# KA2_4.net
KiCad netlist of a schematic drawn in Altium Designer
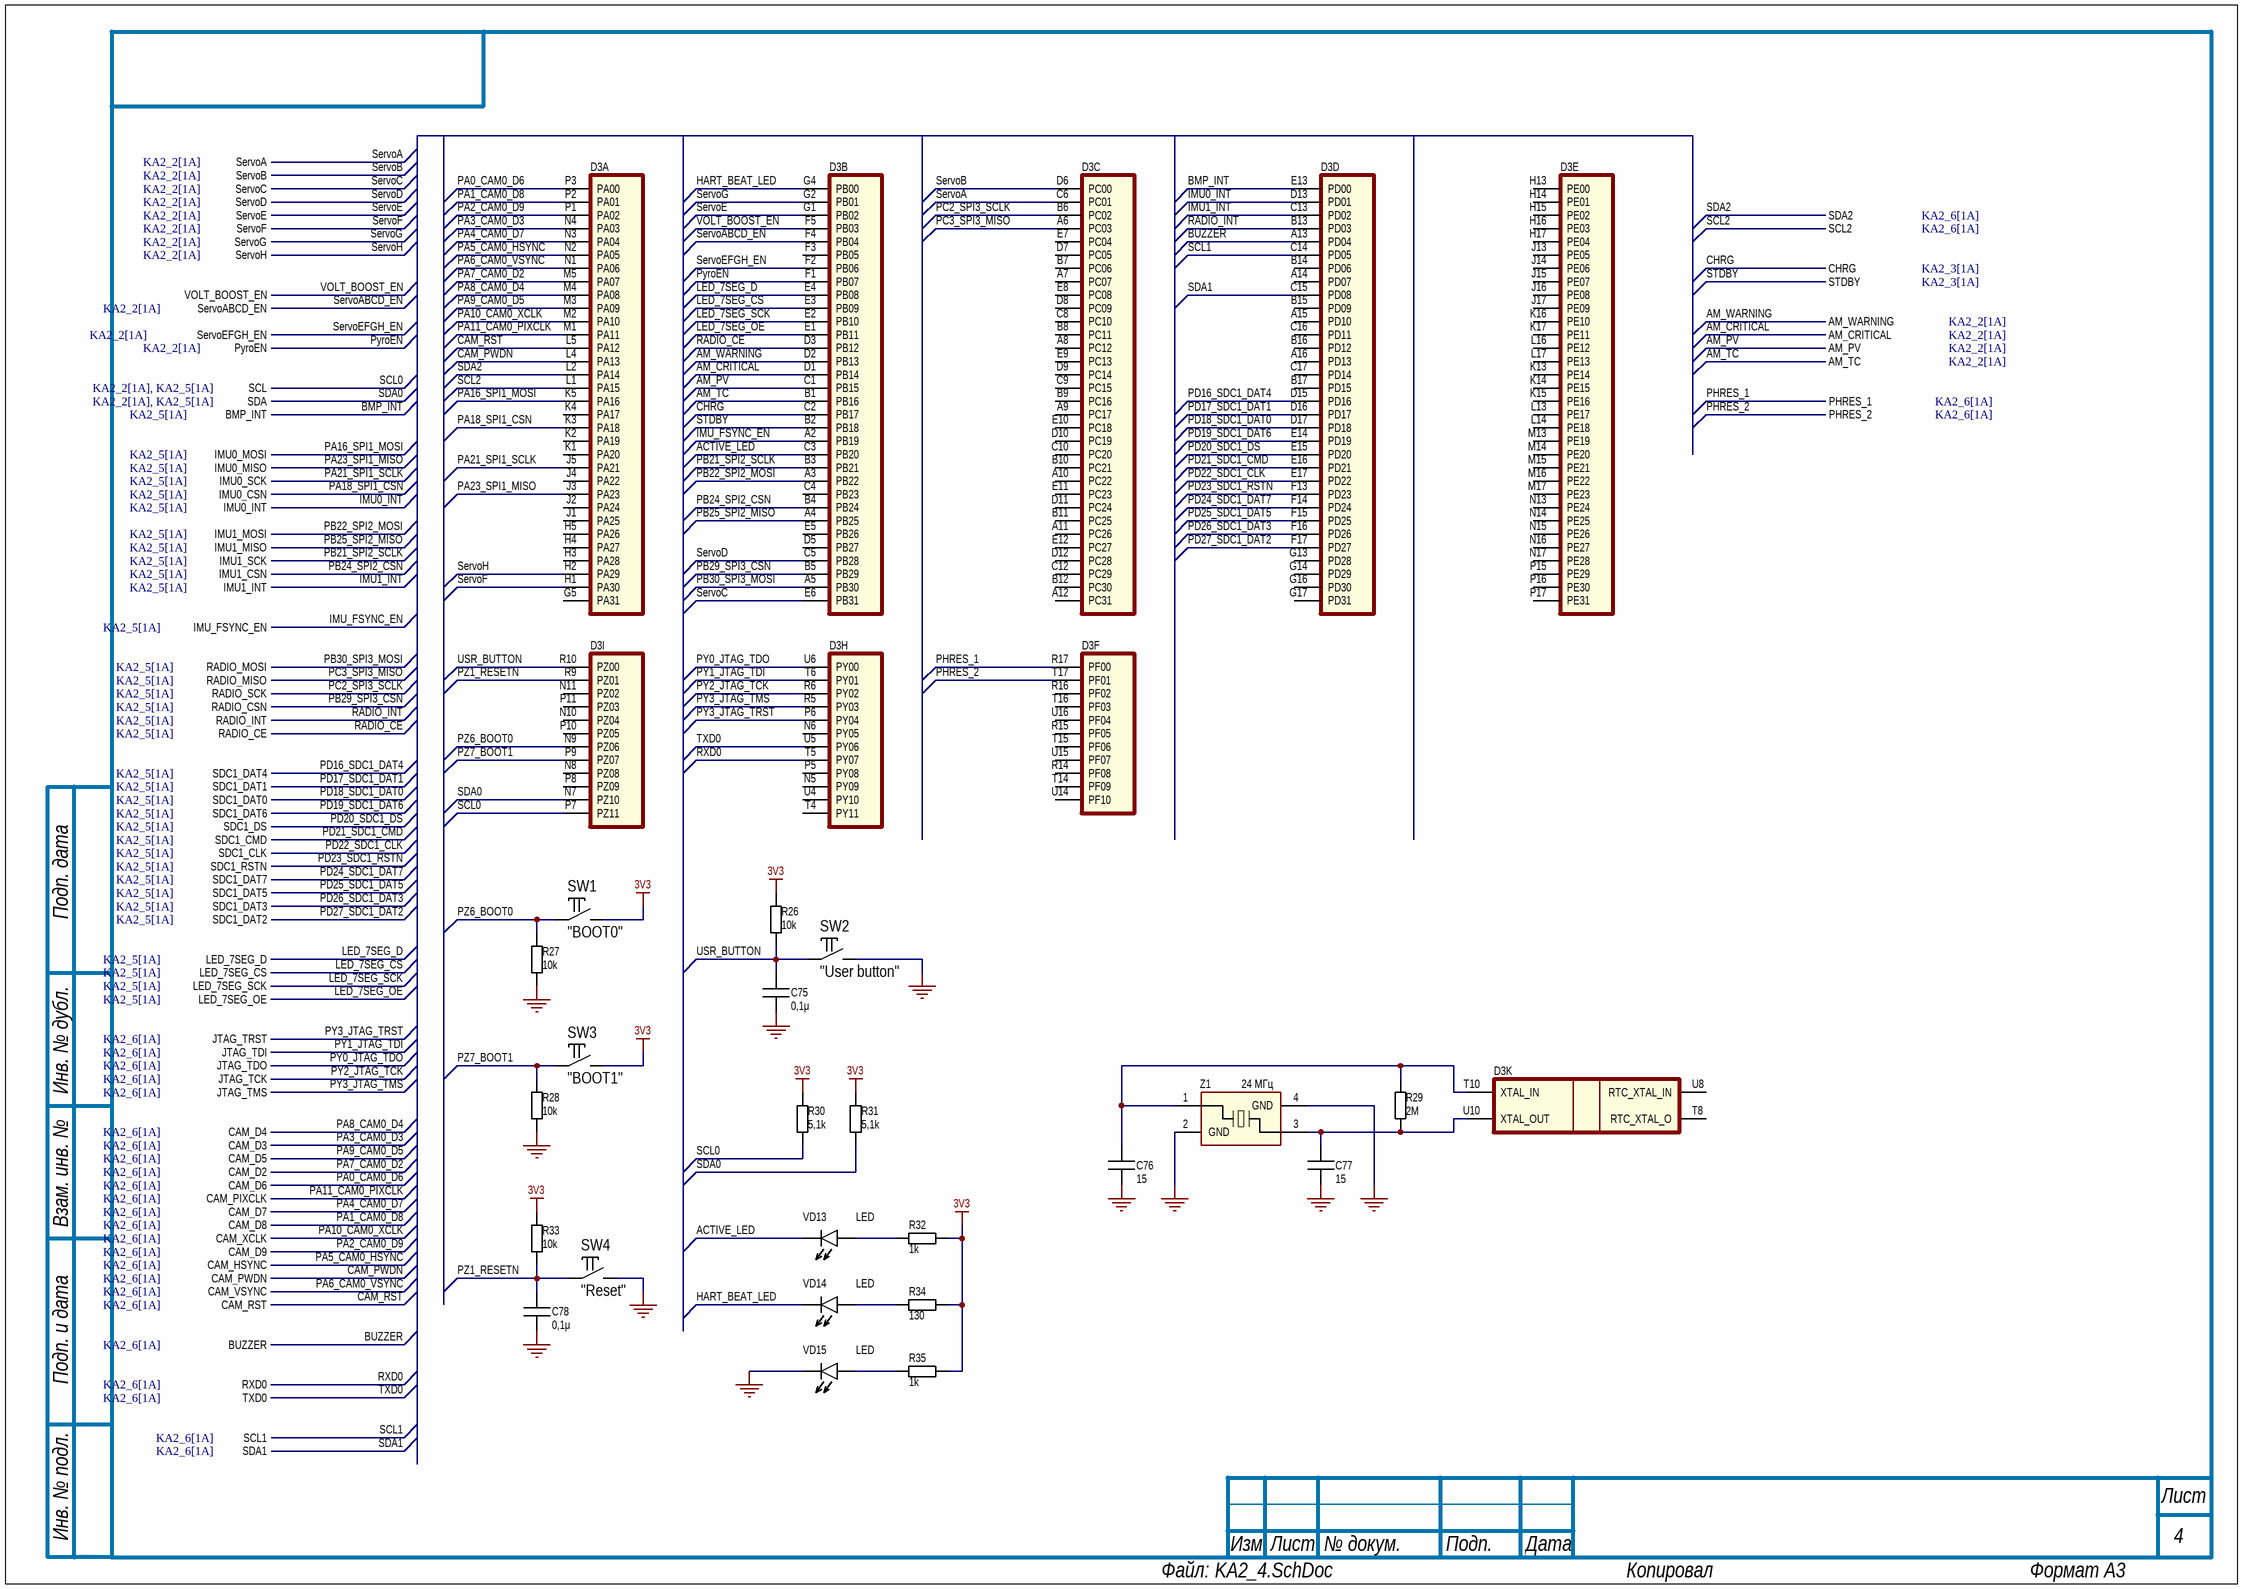
[diagram p0: KA2_4.SchDoc]

(export (version "E")
  (design (tool "Eeschema 10.0.6"))
  (components
    (comp (ref "C75")
      (value "0,1μ")
      (footprint "Capacitor_0402")
      (fields
        (field (name "VALUEMANUFACTURERPARTNUMBER") "Ceramic capacitor, 0,1μ, X7R, ±10%, 16V, 0402")
        (field (name "TOLERANCE") "±10%")
        (field (name "VOLTAGE") "16V")
      )
      (libsource (lib "Barsotion") (part "Ceramic_0402"))
    )
    (comp (ref "C76")
      (value "15")
      (footprint "Capacitor_0402")
      (fields
        (field (name "VALUEMANUFACTURERPARTNUMBER") "Ceramic capacitor, 15, X7R, ±10%, 16V, 0402")
        (field (name "TOLERANCE") "±10%")
        (field (name "VOLTAGE") "16V")
      )
      (libsource (lib "Barsotion") (part "Ceramic_0402"))
    )
    (comp (ref "C77")
      (value "15")
      (footprint "Capacitor_0402")
      (fields
        (field (name "VALUEMANUFACTURERPARTNUMBER") "Ceramic capacitor, 15, X7R, ±10%, 16V, 0402")
        (field (name "TOLERANCE") "±10%")
        (field (name "VOLTAGE") "16V")
      )
      (libsource (lib "Barsotion") (part "Ceramic_0402"))
    )
    (comp (ref "C78")
      (value "0,1μ")
      (footprint "Capacitor_0402")
      (fields
        (field (name "VALUEMANUFACTURERPARTNUMBER") "Ceramic capacitor, 0,1μ, X7R, ±10%, 16V, 0402")
        (field (name "TOLERANCE") "±10%")
        (field (name "VOLTAGE") "16V")
      )
      (libsource (lib "Barsotion") (part "Ceramic_0402"))
    )
    (comp (ref "D3")
      (value "HPM6754IVM2")
      (footprint "HPM6754IVM2_BGA-289_14x14mm")
      (description "Микроконтроллер RISC-V, 2xRV32GCBP@816МГц, 2МБ ОЗУ, BGA-289 14x14mm")
      (fields (field (name "MANUFACTURER") "HPMICRO"))
      (libsource (lib "Barsotion") (part "HPM6754IVM2"))
    )
    (comp (ref "R26")
      (value "10k")
      (footprint "RES: 0402")
      (fields
        (field (name "VALUEMANUFACTURERPARTNUMBER") "Resistor, 10k, ±1%, 0402")
        (field (name "TOLERANCE") "±1%")
      )
      (libsource (lib "Barsotion") (part "Resistor_0402"))
    )
    (comp (ref "R27")
      (value "10k")
      (footprint "RES: 0402")
      (fields
        (field (name "VALUEMANUFACTURERPARTNUMBER") "Resistor, 10k, ±1%, 0402")
        (field (name "TOLERANCE") "±1%")
      )
      (libsource (lib "Barsotion") (part "Resistor_0402"))
    )
    (comp (ref "R28")
      (value "10k")
      (footprint "RES: 0402")
      (fields
        (field (name "VALUEMANUFACTURERPARTNUMBER") "Resistor, 10k, ±1%, 0402")
        (field (name "TOLERANCE") "±1%")
      )
      (libsource (lib "Barsotion") (part "Resistor_0402"))
    )
    (comp (ref "R29")
      (value "2M")
      (footprint "RES: 0402")
      (fields
        (field (name "VALUEMANUFACTURERPARTNUMBER") "Resistor, 2M, ±1%, 0402")
        (field (name "TOLERANCE") "±1%")
      )
      (libsource (lib "Barsotion") (part "Resistor_0402"))
    )
    (comp (ref "R30")
      (value "5,1k")
      (footprint "RES: 0402")
      (fields
        (field (name "VALUEMANUFACTURERPARTNUMBER") "Resistor, 5,1k, ±1%, 0402")
        (field (name "TOLERANCE") "±1%")
      )
      (libsource (lib "Barsotion") (part "Resistor_0402"))
    )
    (comp (ref "R31")
      (value "5,1k")
      (footprint "RES: 0402")
      (fields
        (field (name "VALUEMANUFACTURERPARTNUMBER") "Resistor, 5,1k, ±1%, 0402")
        (field (name "TOLERANCE") "±1%")
      )
      (libsource (lib "Barsotion") (part "Resistor_0402"))
    )
    (comp (ref "R32")
      (value "1k")
      (footprint "RES: 0402")
      (fields
        (field (name "VALUEMANUFACTURERPARTNUMBER") "Resistor, 1k, ±1%, 0402")
        (field (name "TOLERANCE") "±1%")
      )
      (libsource (lib "") (part "Resistor_0402_1"))
    )
    (comp (ref "R33")
      (value "10k")
      (footprint "RES: 0402")
      (fields
        (field (name "VALUEMANUFACTURERPARTNUMBER") "Resistor, 10k, ±1%, 0402")
        (field (name "TOLERANCE") "±1%")
      )
      (libsource (lib "Barsotion") (part "Resistor_0402"))
    )
    (comp (ref "R34")
      (value "130")
      (footprint "RES: 0402")
      (fields
        (field (name "VALUEMANUFACTURERPARTNUMBER") "Resistor, 130, ±1%, 0402")
        (field (name "TOLERANCE") "±1%")
      )
      (libsource (lib "") (part "Resistor_0402_1"))
    )
    (comp (ref "R35")
      (value "1k")
      (footprint "RES: 0402")
      (fields
        (field (name "VALUEMANUFACTURERPARTNUMBER") "Resistor, 1k, ±1%, 0402")
        (field (name "TOLERANCE") "±1%")
      )
      (libsource (lib "") (part "Resistor_0402_1"))
    )
    (comp (ref "SW1")
      (value "Tactile Switch SPST 400gf 2.5mm 4.2mm x 3.2mm Surface Mount")
      (footprint "Button_4.2x2.3mm")
      (description "Микропереключатель SMD, SMD-4P,4.2x3.2mm")
      (fields
        (field (name "MANUFACTURER") "G-Switch")
        (field (name "COMMENTTEXT") "\"BOOT0\"")
        (field (name "MFR.PART") "GT-TC048D-H025-L1")
      )
      (libsource (lib "Barsotion") (part "Switch_GT-TC048D-H025-L1"))
    )
    (comp (ref "SW2")
      (value "Tactile Switch SPST 400gf 2.5mm 4.2mm x 3.2mm Surface Mount")
      (footprint "Button_4.2x2.3mm")
      (description "Микропереключатель SMD, SMD-4P,4.2x3.2mm")
      (fields
        (field (name "MANUFACTURER") "G-Switch")
        (field (name "COMMENTTEXT") "\"User button\"")
        (field (name "MFR.PART") "GT-TC048D-H025-L1")
      )
      (libsource (lib "Barsotion") (part "Switch_GT-TC048D-H025-L1"))
    )
    (comp (ref "SW3")
      (value "Tactile Switch SPST 400gf 2.5mm 4.2mm x 3.2mm Surface Mount")
      (footprint "Button_4.2x2.3mm")
      (description "Микропереключатель SMD, SMD-4P,4.2x3.2mm")
      (fields
        (field (name "MANUFACTURER") "G-Switch")
        (field (name "COMMENTTEXT") "\"BOOT1\"")
        (field (name "MFR.PART") "GT-TC048D-H025-L1")
      )
      (libsource (lib "Barsotion") (part "Switch_GT-TC048D-H025-L1"))
    )
    (comp (ref "SW4")
      (value "Tactile Switch SPST 400gf 2.5mm 4.2mm x 3.2mm Surface Mount")
      (footprint "Button_4.2x2.3mm")
      (description "Микропереключатель SMD, SMD-4P,4.2x3.2mm")
      (fields
        (field (name "MANUFACTURER") "G-Switch")
        (field (name "COMMENTTEXT") "\"Reset\"")
        (field (name "MFR.PART") "GT-TC048D-H025-L1")
      )
      (libsource (lib "Barsotion") (part "Switch_GT-TC048D-H025-L1"))
    )
    (comp (ref "VD13")
      (value "LED")
      (footprint "LED: 0603Y")
      (description "Светодиод желтый, 0603")
      (fields (field (name "MFR.PART") "TJ-S1608CY6T5ALC9Y-A5") (field (name "MANUFACTURER") "TOGIALED"))
      (libsource (lib "Barsotion") (part "LED_0603_Y"))
    )
    (comp (ref "VD14")
      (value "LED")
      (footprint "LED: 0603Y")
      (description "Светодиод белый, 0603")
      (fields (field (name "MFR.PART") "TZ0603W3G-001/2#") (field (name "MANUFACTURER") "TUOZHAN"))
      (libsource (lib "Barsotion") (part "LED_0603_W"))
    )
    (comp (ref "VD15")
      (value "LED")
      (footprint "LED: 0603Y")
      (description "Светодиод желтый, 0603")
      (fields (field (name "MFR.PART") "TJ-S1608CY6T5ALC9Y-A5") (field (name "MANUFACTURER") "TOGIALED"))
      (libsource (lib "Barsotion") (part "LED_0603_Y"))
    )
    (comp (ref "Z1")
      (value "24 МГц")
      (footprint "OSC: 2016")
      (description "Кварцевый резонатор 24 МГц 2016")
      (fields
        (field (name "MFR.PART") "XL7EL89CKI-111YLC-24M")
        (field (name "MANUFACTURER") "YXC Crystal Oscillators")
      )
      (libsource (lib "Barsotion") (part "Crystal_XL7EL89CKI-111YLC-24M"))
    )
  )
  (nets
    (net (code "1") (name "/ACTIVE_LED") (class "Default")
      (node (ref "D3") (pin "C3") (pinfunction "PB20_C3") (pintype "passive"))
      (node (ref "VD13") (pin "K") (pinfunction "Kathode_K") (pintype "passive"))
    )
    (net (code "2") (name "/AM_CRITICAL") (class "Default")
      (node (ref "D3") (pin "D1") (pinfunction "PB14_D1") (pintype "passive"))
    )
    (net (code "3") (name "/AM_PV") (class "Default")
      (node (ref "D3") (pin "C1") (pinfunction "PB15_C1") (pintype "passive"))
    )
    (net (code "4") (name "/AM_TC") (class "Default")
      (node (ref "D3") (pin "B1") (pinfunction "PB16_B1") (pintype "passive"))
    )
    (net (code "5") (name "/AM_WARNING") (class "Default")
      (node (ref "D3") (pin "D2") (pinfunction "PB13_D2") (pintype "passive"))
    )
    (net (code "6") (name "/BMP_INT") (class "Default")
      (node (ref "D3") (pin "E13") (pinfunction "PD00_E13") (pintype "passive"))
    )
    (net (code "7") (name "/BUZZER") (class "Default")
      (node (ref "D3") (pin "A13") (pinfunction "PD04_A13") (pintype "passive"))
    )
    (net (code "8") (name "/CAM_PWDN") (class "Default")
      (node (ref "D3") (pin "L4") (pinfunction "PA13_L4") (pintype "passive"))
    )
    (net (code "9") (name "/CAM_RST") (class "Default")
      (node (ref "D3") (pin "L5") (pinfunction "PA12_L5") (pintype "passive"))
    )
    (net (code "10") (name "/CHRG") (class "Default")
      (node (ref "D3") (pin "C2") (pinfunction "PB17_C2") (pintype "passive"))
    )
    (net (code "11") (name "/HART_BEAT_LED") (class "Default")
      (node (ref "D3") (pin "G4") (pinfunction "PB00_G4") (pintype "passive"))
      (node (ref "VD14") (pin "K") (pinfunction "Kathode_K") (pintype "passive"))
    )
    (net (code "12") (name "/IMU0_INT") (class "Default")
      (node (ref "D3") (pin "D13") (pinfunction "PD01_D13") (pintype "passive"))
    )
    (net (code "13") (name "/IMU1_INT") (class "Default")
      (node (ref "D3") (pin "C13") (pinfunction "PD02_C13") (pintype "passive"))
    )
    (net (code "14") (name "/IMU_FSYNC_EN") (class "Default")
      (node (ref "D3") (pin "A2") (pinfunction "PB19_A2") (pintype "passive"))
    )
    (net (code "15") (name "/LED_7SEG_CS") (class "Default")
      (node (ref "D3") (pin "E3") (pinfunction "PB09_E3") (pintype "passive"))
    )
    (net (code "16") (name "/LED_7SEG_D") (class "Default")
      (node (ref "D3") (pin "E4") (pinfunction "PB08_E4") (pintype "passive"))
    )
    (net (code "17") (name "/LED_7SEG_OE") (class "Default")
      (node (ref "D3") (pin "E1") (pinfunction "PB11_E1") (pintype "passive"))
    )
    (net (code "18") (name "/LED_7SEG_SCK") (class "Default")
      (node (ref "D3") (pin "E2") (pinfunction "PB10_E2") (pintype "passive"))
    )
    (net (code "19") (name "/PA0_CAM0_D6") (class "Default")
      (node (ref "D3") (pin "P3") (pinfunction "PA00_P3") (pintype "passive"))
    )
    (net (code "20") (name "/PA1_CAM0_D8") (class "Default")
      (node (ref "D3") (pin "P2") (pinfunction "PA01_P2") (pintype "passive"))
    )
    (net (code "21") (name "/PA2_CAM0_D9") (class "Default")
      (node (ref "D3") (pin "P1") (pinfunction "PA02_P1") (pintype "passive"))
    )
    (net (code "22") (name "/PA3_CAM0_D3") (class "Default")
      (node (ref "D3") (pin "N4") (pinfunction "PA03_N4") (pintype "passive"))
    )
    (net (code "23") (name "/PA4_CAM0_D7") (class "Default")
      (node (ref "D3") (pin "N3") (pinfunction "PA04_N3") (pintype "passive"))
    )
    (net (code "24") (name "/PA5_CAM0_HSYNC") (class "Default")
      (node (ref "D3") (pin "N2") (pinfunction "PA05_N2") (pintype "passive"))
    )
    (net (code "25") (name "/PA6_CAM0_VSYNC") (class "Default")
      (node (ref "D3") (pin "N1") (pinfunction "PA06_N1") (pintype "passive"))
    )
    (net (code "26") (name "/PA7_CAM0_D2") (class "Default")
      (node (ref "D3") (pin "M5") (pinfunction "PA07_M5") (pintype "passive"))
    )
    (net (code "27") (name "/PA8_CAM0_D4") (class "Default")
      (node (ref "D3") (pin "M4") (pinfunction "PA08_M4") (pintype "passive"))
    )
    (net (code "28") (name "/PA9_CAM0_D5") (class "Default")
      (node (ref "D3") (pin "M3") (pinfunction "PA09_M3") (pintype "passive"))
    )
    (net (code "29") (name "/PA10_CAM0_XCLK") (class "Default")
      (node (ref "D3") (pin "M2") (pinfunction "PA10_M2") (pintype "passive"))
    )
    (net (code "30") (name "/PA11_CAM0_PIXCLK") (class "Default")
      (node (ref "D3") (pin "M1") (pinfunction "PA11_M1") (pintype "passive"))
    )
    (net (code "31") (name "/PA16_SPI1_MOSI") (class "Default")
      (node (ref "D3") (pin "K5") (pinfunction "PA16_K5") (pintype "passive"))
    )
    (net (code "32") (name "/PA18_SPI1_CSN") (class "Default")
      (node (ref "D3") (pin "K3") (pinfunction "PA18_K3") (pintype "passive"))
    )
    (net (code "33") (name "/PA21_SPI1_SCLK") (class "Default")
      (node (ref "D3") (pin "J5") (pinfunction "PA21_J5") (pintype "passive"))
    )
    (net (code "34") (name "/PA23_SPI1_MISO") (class "Default")
      (node (ref "D3") (pin "J3") (pinfunction "PA23_J3") (pintype "passive"))
    )
    (net (code "35") (name "/PB21_SPI2_SCLK") (class "Default")
      (node (ref "D3") (pin "B3") (pinfunction "PB21_B3") (pintype "passive"))
    )
    (net (code "36") (name "/PB22_SPI2_MOSI") (class "Default")
      (node (ref "D3") (pin "A3") (pinfunction "PB22_A3") (pintype "passive"))
    )
    (net (code "37") (name "/PB24_SPI2_CSN") (class "Default")
      (node (ref "D3") (pin "B4") (pinfunction "PB24_B4") (pintype "passive"))
    )
    (net (code "38") (name "/PB25_SPI2_MISO") (class "Default")
      (node (ref "D3") (pin "A4") (pinfunction "PB25_A4") (pintype "passive"))
    )
    (net (code "39") (name "/PB29_SPI3_CSN") (class "Default")
      (node (ref "D3") (pin "B5") (pinfunction "PB29_B5") (pintype "passive"))
    )
    (net (code "40") (name "/PB30_SPI3_MOSI") (class "Default")
      (node (ref "D3") (pin "A5") (pinfunction "PB30_A5") (pintype "passive"))
    )
    (net (code "41") (name "/PC2_SPI3_SCLK") (class "Default")
      (node (ref "D3") (pin "B6") (pinfunction "PC02_B6") (pintype "passive"))
    )
    (net (code "42") (name "/PC3_SPI3_MISO") (class "Default")
      (node (ref "D3") (pin "A6") (pinfunction "PC03_A6") (pintype "passive"))
    )
    (net (code "43") (name "/PD16_SDC1_DAT4") (class "Default")
      (node (ref "D3") (pin "D15") (pinfunction "PD16_D15") (pintype "passive"))
    )
    (net (code "44") (name "/PD17_SDC1_DAT1") (class "Default")
      (node (ref "D3") (pin "D16") (pinfunction "PD17_D16") (pintype "passive"))
    )
    (net (code "45") (name "/PD18_SDC1_DAT0") (class "Default")
      (node (ref "D3") (pin "D17") (pinfunction "PD18_D17") (pintype "passive"))
    )
    (net (code "46") (name "/PD19_SDC1_DAT6") (class "Default")
      (node (ref "D3") (pin "E14") (pinfunction "PD19_E14") (pintype "passive"))
    )
    (net (code "47") (name "/PD20_SDC1_DS") (class "Default")
      (node (ref "D3") (pin "E15") (pinfunction "PD20_E15") (pintype "passive"))
    )
    (net (code "48") (name "/PD21_SDC1_CMD") (class "Default")
      (node (ref "D3") (pin "E16") (pinfunction "PD21_E16") (pintype "passive"))
    )
    (net (code "49") (name "/PD22_SDC1_CLK") (class "Default")
      (node (ref "D3") (pin "E17") (pinfunction "PD22_E17") (pintype "passive"))
    )
    (net (code "50") (name "/PD23_SDC1_RSTN") (class "Default")
      (node (ref "D3") (pin "F13") (pinfunction "PD23_F13") (pintype "passive"))
    )
    (net (code "51") (name "/PD24_SDC1_DAT7") (class "Default")
      (node (ref "D3") (pin "F14") (pinfunction "PD24_F14") (pintype "passive"))
    )
    (net (code "52") (name "/PD25_SDC1_DAT5") (class "Default")
      (node (ref "D3") (pin "F15") (pinfunction "PD25_F15") (pintype "passive"))
    )
    (net (code "53") (name "/PD26_SDC1_DAT3") (class "Default")
      (node (ref "D3") (pin "F16") (pinfunction "PD26_F16") (pintype "passive"))
    )
    (net (code "54") (name "/PD27_SDC1_DAT2") (class "Default")
      (node (ref "D3") (pin "F17") (pinfunction "PD27_F17") (pintype "passive"))
    )
    (net (code "55") (name "/PHRES_1") (class "Default")
      (node (ref "D3") (pin "R17") (pinfunction "PF00_R17") (pintype "passive"))
    )
    (net (code "56") (name "/PHRES_2") (class "Default")
      (node (ref "D3") (pin "T17") (pinfunction "PF01_T17") (pintype "passive"))
    )
    (net (code "57") (name "/PY0_JTAG_TDO") (class "Default")
      (node (ref "D3") (pin "U6") (pinfunction "PY00_U6") (pintype "passive"))
    )
    (net (code "58") (name "/PY1_JTAG_TDI") (class "Default")
      (node (ref "D3") (pin "T6") (pinfunction "PY01_T6") (pintype "passive"))
    )
    (net (code "59") (name "/PY2_JTAG_TCK") (class "Default")
      (node (ref "D3") (pin "R6") (pinfunction "PY02_R6") (pintype "passive"))
    )
    (net (code "60") (name "/PY3_JTAG_TMS") (class "Default")
      (node (ref "D3") (pin "R5") (pinfunction "PY03_R5") (pintype "passive"))
    )
    (net (code "61") (name "/PY3_JTAG_TRST") (class "Default")
      (node (ref "D3") (pin "P6") (pinfunction "PY04_P6") (pintype "passive"))
    )
    (net (code "62") (name "/PZ1_RESETN") (class "Default")
      (node (ref "C78") (pin "2") (pinfunction "2_2") (pintype "passive"))
      (node (ref "D3") (pin "R9") (pinfunction "PZ01_R9") (pintype "passive"))
      (node (ref "R33") (pin "1") (pinfunction "1_1") (pintype "passive"))
      (node (ref "SW4") (pin "1") (pinfunction "1_1") (pintype "passive"))
    )
    (net (code "63") (name "/PZ6_BOOT0") (class "Default")
      (node (ref "D3") (pin "N9") (pinfunction "PZ06_N9") (pintype "passive"))
      (node (ref "R27") (pin "2") (pinfunction "2_2") (pintype "passive"))
      (node (ref "SW1") (pin "1") (pinfunction "1_1") (pintype "passive"))
    )
    (net (code "64") (name "/PZ7_BOOT1") (class "Default")
      (node (ref "D3") (pin "P9") (pinfunction "PZ07_P9") (pintype "passive"))
      (node (ref "R28") (pin "2") (pinfunction "2_2") (pintype "passive"))
      (node (ref "SW3") (pin "1") (pinfunction "1_1") (pintype "passive"))
    )
    (net (code "65") (name "/PyroEN") (class "Default")
      (node (ref "D3") (pin "F1") (pinfunction "PB07_F1") (pintype "passive"))
    )
    (net (code "66") (name "/RADIO_CE") (class "Default")
      (node (ref "D3") (pin "D3") (pinfunction "PB12_D3") (pintype "passive"))
    )
    (net (code "67") (name "/RADIO_INT") (class "Default")
      (node (ref "D3") (pin "B13") (pinfunction "PD03_B13") (pintype "passive"))
    )
    (net (code "68") (name "/RXD0") (class "Default")
      (node (ref "D3") (pin "T5") (pinfunction "PY07_T5") (pintype "passive"))
    )
    (net (code "69") (name "/SCL0") (class "Default")
      (node (ref "D3") (pin "P7") (pinfunction "PZ11_P7") (pintype "passive"))
      (node (ref "R30") (pin "1") (pinfunction "1_1") (pintype "passive"))
    )
    (net (code "70") (name "/SCL1") (class "Default")
      (node (ref "D3") (pin "C14") (pinfunction "PD05_C14") (pintype "passive"))
    )
    (net (code "71") (name "/SCL2") (class "Default")
      (node (ref "D3") (pin "L1") (pinfunction "PA15_L1") (pintype "passive"))
    )
    (net (code "72") (name "/SDA0") (class "Default")
      (node (ref "D3") (pin "N7") (pinfunction "PZ10_N7") (pintype "passive"))
      (node (ref "R31") (pin "1") (pinfunction "1_1") (pintype "passive"))
    )
    (net (code "73") (name "/SDA1") (class "Default")
      (node (ref "D3") (pin "C15") (pinfunction "PD08_C15") (pintype "passive"))
    )
    (net (code "74") (name "/SDA2") (class "Default")
      (node (ref "D3") (pin "L2") (pinfunction "PA14_L2") (pintype "passive"))
    )
    (net (code "75") (name "/STDBY") (class "Default")
      (node (ref "D3") (pin "B2") (pinfunction "PB18_B2") (pintype "passive"))
    )
    (net (code "76") (name "/ServoA") (class "Default")
      (node (ref "D3") (pin "C6") (pinfunction "PC01_C6") (pintype "passive"))
    )
    (net (code "77") (name "/ServoABCD_EN") (class "Default")
      (node (ref "D3") (pin "F4") (pinfunction "PB04_F4") (pintype "passive"))
    )
    (net (code "78") (name "/ServoB") (class "Default")
      (node (ref "D3") (pin "D6") (pinfunction "PC00_D6") (pintype "passive"))
    )
    (net (code "79") (name "/ServoC") (class "Default")
      (node (ref "D3") (pin "E6") (pinfunction "PB31_E6") (pintype "passive"))
    )
    (net (code "80") (name "/ServoD") (class "Default")
      (node (ref "D3") (pin "C5") (pinfunction "PB28_C5") (pintype "passive"))
    )
    (net (code "81") (name "/ServoE") (class "Default")
      (node (ref "D3") (pin "G1") (pinfunction "PB02_G1") (pintype "passive"))
    )
    (net (code "82") (name "/ServoEFGH_EN") (class "Default")
      (node (ref "D3") (pin "F2") (pinfunction "PB06_F2") (pintype "passive"))
    )
    (net (code "83") (name "/ServoF") (class "Default")
      (node (ref "D3") (pin "H1") (pinfunction "PA30_H1") (pintype "passive"))
    )
    (net (code "84") (name "/ServoG") (class "Default")
      (node (ref "D3") (pin "G2") (pinfunction "PB01_G2") (pintype "passive"))
    )
    (net (code "85") (name "/ServoH") (class "Default")
      (node (ref "D3") (pin "H2") (pinfunction "PA29_H2") (pintype "passive"))
    )
    (net (code "86") (name "/TXD0") (class "Default")
      (node (ref "D3") (pin "U5") (pinfunction "PY06_U5") (pintype "passive"))
    )
    (net (code "87") (name "/USR_BUTTON") (class "Default")
      (node (ref "C75") (pin "2") (pinfunction "2_2") (pintype "passive"))
      (node (ref "D3") (pin "R10") (pinfunction "PZ00_R10") (pintype "passive"))
      (node (ref "R26") (pin "1") (pinfunction "1_1") (pintype "passive"))
      (node (ref "SW2") (pin "1") (pinfunction "1_1") (pintype "passive"))
    )
    (net (code "88") (name "/VOLT_BOOST_EN") (class "Default")
      (node (ref "D3") (pin "F5") (pinfunction "PB03_F5") (pintype "passive"))
    )
    (net (code "89") (name "3V3") (class "Default")
      (node (ref "R26") (pin "2") (pinfunction "2_2") (pintype "passive"))
      (node (ref "R30") (pin "2") (pinfunction "2_2") (pintype "passive"))
      (node (ref "R31") (pin "2") (pinfunction "2_2") (pintype "passive"))
      (node (ref "R32") (pin "1") (pinfunction "1_1") (pintype "passive"))
      (node (ref "R33") (pin "2") (pinfunction "2_2") (pintype "passive"))
      (node (ref "R34") (pin "1") (pinfunction "1_1") (pintype "passive"))
      (node (ref "R35") (pin "1") (pinfunction "1_1") (pintype "passive"))
      (node (ref "SW1") (pin "2") (pinfunction "2_2") (pintype "passive"))
      (node (ref "SW3") (pin "2") (pinfunction "2_2") (pintype "passive"))
    )
    (net (code "90") (name "GND") (class "Default")
      (node (ref "C75") (pin "1") (pinfunction "1_1") (pintype "passive"))
      (node (ref "C76") (pin "1") (pinfunction "1_1") (pintype "passive"))
      (node (ref "C77") (pin "1") (pinfunction "1_1") (pintype "passive"))
      (node (ref "C78") (pin "1") (pinfunction "1_1") (pintype "passive"))
      (node (ref "R27") (pin "1") (pinfunction "1_1") (pintype "passive"))
      (node (ref "R28") (pin "1") (pinfunction "1_1") (pintype "passive"))
      (node (ref "SW2") (pin "2") (pinfunction "2_2") (pintype "passive"))
      (node (ref "SW4") (pin "2") (pinfunction "2_2") (pintype "passive"))
      (node (ref "VD15") (pin "K") (pinfunction "Kathode_K") (pintype "passive"))
      (node (ref "Z1") (pin "2") (pinfunction "GND_2") (pintype "passive"))
      (node (ref "Z1") (pin "4") (pinfunction "GND_4") (pintype "passive"))
    )
    (net (code "91") (name "Net-(D3K-XTAL_IN)") (class "Default")
      (node (ref "C76") (pin "2") (pinfunction "2_2") (pintype "passive"))
      (node (ref "D3") (pin "T10") (pinfunction "XTAL_IN_T10") (pintype "passive"))
      (node (ref "R29") (pin "2") (pinfunction "2_2") (pintype "passive"))
      (node (ref "Z1") (pin "1") (pinfunction "X1_1") (pintype "passive"))
    )
    (net (code "92") (name "Net-(D3K-XTAL_OUT)") (class "Default")
      (node (ref "C77") (pin "2") (pinfunction "2_2") (pintype "passive"))
      (node (ref "D3") (pin "U10") (pinfunction "XTAL_OUT_U10") (pintype "passive"))
      (node (ref "R29") (pin "1") (pinfunction "1_1") (pintype "passive"))
      (node (ref "Z1") (pin "3") (pinfunction "X2_3") (pintype "passive"))
    )
    (net (code "93") (name "Net-(VD13-Anode)") (class "Default")
      (node (ref "R32") (pin "2") (pinfunction "2_2") (pintype "passive"))
      (node (ref "VD13") (pin "A") (pinfunction "Anode_A") (pintype "passive"))
    )
    (net (code "94") (name "Net-(VD14-Anode)") (class "Default")
      (node (ref "R34") (pin "2") (pinfunction "2_2") (pintype "passive"))
      (node (ref "VD14") (pin "A") (pinfunction "Anode_A") (pintype "passive"))
    )
    (net (code "95") (name "Net-(VD15-Anode)") (class "Default")
      (node (ref "R35") (pin "2") (pinfunction "2_2") (pintype "passive"))
      (node (ref "VD15") (pin "A") (pinfunction "Anode_A") (pintype "passive"))
    )
    (net (code "96") (name "unconnected-(D3A-PA17-PadK4)") (class "Default")
      (node (ref "D3") (pin "K4") (pinfunction "PA17_K4") (pintype "passive"))
    )
    (net (code "97") (name "unconnected-(D3A-PA19-PadK2)") (class "Default")
      (node (ref "D3") (pin "K2") (pinfunction "PA19_K2") (pintype "passive"))
    )
    (net (code "98") (name "unconnected-(D3A-PA20-PadK1)") (class "Default")
      (node (ref "D3") (pin "K1") (pinfunction "PA20_K1") (pintype "passive"))
    )
    (net (code "99") (name "unconnected-(D3A-PA22-PadJ4)") (class "Default")
      (node (ref "D3") (pin "J4") (pinfunction "PA22_J4") (pintype "passive"))
    )
    (net (code "100") (name "unconnected-(D3A-PA24-PadJ2)") (class "Default")
      (node (ref "D3") (pin "J2") (pinfunction "PA24_J2") (pintype "passive"))
    )
    (net (code "101") (name "unconnected-(D3A-PA25-PadJ1)") (class "Default")
      (node (ref "D3") (pin "J1") (pinfunction "PA25_J1") (pintype "passive"))
    )
    (net (code "102") (name "unconnected-(D3A-PA26-PadH5)") (class "Default")
      (node (ref "D3") (pin "H5") (pinfunction "PA26_H5") (pintype "passive"))
    )
    (net (code "103") (name "unconnected-(D3A-PA27-PadH4)") (class "Default")
      (node (ref "D3") (pin "H4") (pinfunction "PA27_H4") (pintype "passive"))
    )
    (net (code "104") (name "unconnected-(D3A-PA28-PadH3)") (class "Default")
      (node (ref "D3") (pin "H3") (pinfunction "PA28_H3") (pintype "passive"))
    )
    (net (code "105") (name "unconnected-(D3A-PA31-PadG5)") (class "Default")
      (node (ref "D3") (pin "G5") (pinfunction "PA31_G5") (pintype "passive"))
    )
    (net (code "106") (name "unconnected-(D3B-PB05-PadF3)") (class "Default")
      (node (ref "D3") (pin "F3") (pinfunction "PB05_F3") (pintype "passive"))
    )
    (net (code "107") (name "unconnected-(D3B-PB23-PadC4)") (class "Default")
      (node (ref "D3") (pin "C4") (pinfunction "PB23_C4") (pintype "passive"))
    )
    (net (code "108") (name "unconnected-(D3B-PB26-PadE5)") (class "Default")
      (node (ref "D3") (pin "E5") (pinfunction "PB26_E5") (pintype "passive"))
    )
    (net (code "109") (name "unconnected-(D3B-PB27-PadD5)") (class "Default")
      (node (ref "D3") (pin "D5") (pinfunction "PB27_D5") (pintype "passive"))
    )
    (net (code "110") (name "unconnected-(D3C-PC04-PadE7)") (class "Default")
      (node (ref "D3") (pin "E7") (pinfunction "PC04_E7") (pintype "passive"))
    )
    (net (code "111") (name "unconnected-(D3C-PC05-PadD7)") (class "Default")
      (node (ref "D3") (pin "D7") (pinfunction "PC05_D7") (pintype "passive"))
    )
    (net (code "112") (name "unconnected-(D3C-PC06-PadB7)") (class "Default")
      (node (ref "D3") (pin "B7") (pinfunction "PC06_B7") (pintype "passive"))
    )
    (net (code "113") (name "unconnected-(D3C-PC07-PadA7)") (class "Default")
      (node (ref "D3") (pin "A7") (pinfunction "PC07_A7") (pintype "passive"))
    )
    (net (code "114") (name "unconnected-(D3C-PC08-PadE8)") (class "Default")
      (node (ref "D3") (pin "E8") (pinfunction "PC08_E8") (pintype "passive"))
    )
    (net (code "115") (name "unconnected-(D3C-PC09-PadD8)") (class "Default")
      (node (ref "D3") (pin "D8") (pinfunction "PC09_D8") (pintype "passive"))
    )
    (net (code "116") (name "unconnected-(D3C-PC10-PadC8)") (class "Default")
      (node (ref "D3") (pin "C8") (pinfunction "PC10_C8") (pintype "passive"))
    )
    (net (code "117") (name "unconnected-(D3C-PC11-PadB8)") (class "Default")
      (node (ref "D3") (pin "B8") (pinfunction "PC11_B8") (pintype "passive"))
    )
    (net (code "118") (name "unconnected-(D3C-PC12-PadA8)") (class "Default")
      (node (ref "D3") (pin "A8") (pinfunction "PC12_A8") (pintype "passive"))
    )
    (net (code "119") (name "unconnected-(D3C-PC13-PadE9)") (class "Default")
      (node (ref "D3") (pin "E9") (pinfunction "PC13_E9") (pintype "passive"))
    )
    (net (code "120") (name "unconnected-(D3C-PC14-PadD9)") (class "Default")
      (node (ref "D3") (pin "D9") (pinfunction "PC14_D9") (pintype "passive"))
    )
    (net (code "121") (name "unconnected-(D3C-PC15-PadC9)") (class "Default")
      (node (ref "D3") (pin "C9") (pinfunction "PC15_C9") (pintype "passive"))
    )
    (net (code "122") (name "unconnected-(D3C-PC16-PadB9)") (class "Default")
      (node (ref "D3") (pin "B9") (pinfunction "PC16_B9") (pintype "passive"))
    )
    (net (code "123") (name "unconnected-(D3C-PC17-PadA9)") (class "Default")
      (node (ref "D3") (pin "A9") (pinfunction "PC17_A9") (pintype "passive"))
    )
    (net (code "124") (name "unconnected-(D3C-PC18-PadE10)") (class "Default")
      (node (ref "D3") (pin "E10") (pinfunction "PC18_E10") (pintype "passive"))
    )
    (net (code "125") (name "unconnected-(D3C-PC19-PadD10)") (class "Default")
      (node (ref "D3") (pin "D10") (pinfunction "PC19_D10") (pintype "passive"))
    )
    (net (code "126") (name "unconnected-(D3C-PC20-PadC10)") (class "Default")
      (node (ref "D3") (pin "C10") (pinfunction "PC20_C10") (pintype "passive"))
    )
    (net (code "127") (name "unconnected-(D3C-PC21-PadB10)") (class "Default")
      (node (ref "D3") (pin "B10") (pinfunction "PC21_B10") (pintype "passive"))
    )
    (net (code "128") (name "unconnected-(D3C-PC22-PadA10)") (class "Default")
      (node (ref "D3") (pin "A10") (pinfunction "PC22_A10") (pintype "passive"))
    )
    (net (code "129") (name "unconnected-(D3C-PC23-PadE11)") (class "Default")
      (node (ref "D3") (pin "E11") (pinfunction "PC23_E11") (pintype "passive"))
    )
    (net (code "130") (name "unconnected-(D3C-PC24-PadD11)") (class "Default")
      (node (ref "D3") (pin "D11") (pinfunction "PC24_D11") (pintype "passive"))
    )
    (net (code "131") (name "unconnected-(D3C-PC25-PadB11)") (class "Default")
      (node (ref "D3") (pin "B11") (pinfunction "PC25_B11") (pintype "passive"))
    )
    (net (code "132") (name "unconnected-(D3C-PC26-PadA11)") (class "Default")
      (node (ref "D3") (pin "A11") (pinfunction "PC26_A11") (pintype "passive"))
    )
    (net (code "133") (name "unconnected-(D3C-PC27-PadE12)") (class "Default")
      (node (ref "D3") (pin "E12") (pinfunction "PC27_E12") (pintype "passive"))
    )
    (net (code "134") (name "unconnected-(D3C-PC28-PadD12)") (class "Default")
      (node (ref "D3") (pin "D12") (pinfunction "PC28_D12") (pintype "passive"))
    )
    (net (code "135") (name "unconnected-(D3C-PC29-PadC12)") (class "Default")
      (node (ref "D3") (pin "C12") (pinfunction "PC29_C12") (pintype "passive"))
    )
    (net (code "136") (name "unconnected-(D3C-PC30-PadB12)") (class "Default")
      (node (ref "D3") (pin "B12") (pinfunction "PC30_B12") (pintype "passive"))
    )
    (net (code "137") (name "unconnected-(D3C-PC31-PadA12)") (class "Default")
      (node (ref "D3") (pin "A12") (pinfunction "PC31_A12") (pintype "passive"))
    )
    (net (code "138") (name "unconnected-(D3D-PD06-PadB14)") (class "Default")
      (node (ref "D3") (pin "B14") (pinfunction "PD06_B14") (pintype "passive"))
    )
    (net (code "139") (name "unconnected-(D3D-PD07-PadA14)") (class "Default")
      (node (ref "D3") (pin "A14") (pinfunction "PD07_A14") (pintype "passive"))
    )
    (net (code "140") (name "unconnected-(D3D-PD09-PadB15)") (class "Default")
      (node (ref "D3") (pin "B15") (pinfunction "PD09_B15") (pintype "passive"))
    )
    (net (code "141") (name "unconnected-(D3D-PD10-PadA15)") (class "Default")
      (node (ref "D3") (pin "A15") (pinfunction "PD10_A15") (pintype "passive"))
    )
    (net (code "142") (name "unconnected-(D3D-PD11-PadC16)") (class "Default")
      (node (ref "D3") (pin "C16") (pinfunction "PD11_C16") (pintype "passive"))
    )
    (net (code "143") (name "unconnected-(D3D-PD12-PadB16)") (class "Default")
      (node (ref "D3") (pin "B16") (pinfunction "PD12_B16") (pintype "passive"))
    )
    (net (code "144") (name "unconnected-(D3D-PD13-PadA16)") (class "Default")
      (node (ref "D3") (pin "A16") (pinfunction "PD13_A16") (pintype "passive"))
    )
    (net (code "145") (name "unconnected-(D3D-PD14-PadC17)") (class "Default")
      (node (ref "D3") (pin "C17") (pinfunction "PD14_C17") (pintype "passive"))
    )
    (net (code "146") (name "unconnected-(D3D-PD15-PadB17)") (class "Default")
      (node (ref "D3") (pin "B17") (pinfunction "PD15_B17") (pintype "passive"))
    )
    (net (code "147") (name "unconnected-(D3D-PD28-PadG13)") (class "Default")
      (node (ref "D3") (pin "G13") (pinfunction "PD28_G13") (pintype "passive"))
    )
    (net (code "148") (name "unconnected-(D3D-PD29-PadG14)") (class "Default")
      (node (ref "D3") (pin "G14") (pinfunction "PD29_G14") (pintype "passive"))
    )
    (net (code "149") (name "unconnected-(D3D-PD30-PadG16)") (class "Default")
      (node (ref "D3") (pin "G16") (pinfunction "PD30_G16") (pintype "passive"))
    )
    (net (code "150") (name "unconnected-(D3D-PD31-PadG17)") (class "Default")
      (node (ref "D3") (pin "G17") (pinfunction "PD31_G17") (pintype "passive"))
    )
    (net (code "151") (name "unconnected-(D3E-PE00-PadH13)") (class "Default")
      (node (ref "D3") (pin "H13") (pinfunction "PE00_H13") (pintype "passive"))
    )
    (net (code "152") (name "unconnected-(D3E-PE01-PadH14)") (class "Default")
      (node (ref "D3") (pin "H14") (pinfunction "PE01_H14") (pintype "passive"))
    )
    (net (code "153") (name "unconnected-(D3E-PE02-PadH15)") (class "Default")
      (node (ref "D3") (pin "H15") (pinfunction "PE02_H15") (pintype "passive"))
    )
    (net (code "154") (name "unconnected-(D3E-PE03-PadH16)") (class "Default")
      (node (ref "D3") (pin "H16") (pinfunction "PE03_H16") (pintype "passive"))
    )
    (net (code "155") (name "unconnected-(D3E-PE04-PadH17)") (class "Default")
      (node (ref "D3") (pin "H17") (pinfunction "PE04_H17") (pintype "passive"))
    )
    (net (code "156") (name "unconnected-(D3E-PE05-PadJ13)") (class "Default")
      (node (ref "D3") (pin "J13") (pinfunction "PE05_J13") (pintype "passive"))
    )
    (net (code "157") (name "unconnected-(D3E-PE06-PadJ14)") (class "Default")
      (node (ref "D3") (pin "J14") (pinfunction "PE06_J14") (pintype "passive"))
    )
    (net (code "158") (name "unconnected-(D3E-PE07-PadJ15)") (class "Default")
      (node (ref "D3") (pin "J15") (pinfunction "PE07_J15") (pintype "passive"))
    )
    (net (code "159") (name "unconnected-(D3E-PE08-PadJ16)") (class "Default")
      (node (ref "D3") (pin "J16") (pinfunction "PE08_J16") (pintype "passive"))
    )
    (net (code "160") (name "unconnected-(D3E-PE09-PadJ17)") (class "Default")
      (node (ref "D3") (pin "J17") (pinfunction "PE09_J17") (pintype "passive"))
    )
    (net (code "161") (name "unconnected-(D3E-PE10-PadK16)") (class "Default")
      (node (ref "D3") (pin "K16") (pinfunction "PE10_K16") (pintype "passive"))
    )
    (net (code "162") (name "unconnected-(D3E-PE11-PadK17)") (class "Default")
      (node (ref "D3") (pin "K17") (pinfunction "PE11_K17") (pintype "passive"))
    )
    (net (code "163") (name "unconnected-(D3E-PE12-PadL16)") (class "Default")
      (node (ref "D3") (pin "L16") (pinfunction "PE12_L16") (pintype "passive"))
    )
    (net (code "164") (name "unconnected-(D3E-PE13-PadL17)") (class "Default")
      (node (ref "D3") (pin "L17") (pinfunction "PE13_L17") (pintype "passive"))
    )
    (net (code "165") (name "unconnected-(D3E-PE14-PadK13)") (class "Default")
      (node (ref "D3") (pin "K13") (pinfunction "PE14_K13") (pintype "passive"))
    )
    (net (code "166") (name "unconnected-(D3E-PE15-PadK14)") (class "Default")
      (node (ref "D3") (pin "K14") (pinfunction "PE15_K14") (pintype "passive"))
    )
    (net (code "167") (name "unconnected-(D3E-PE16-PadK15)") (class "Default")
      (node (ref "D3") (pin "K15") (pinfunction "PE16_K15") (pintype "passive"))
    )
    (net (code "168") (name "unconnected-(D3E-PE17-PadL13)") (class "Default")
      (node (ref "D3") (pin "L13") (pinfunction "PE17_L13") (pintype "passive"))
    )
    (net (code "169") (name "unconnected-(D3E-PE18-PadL14)") (class "Default")
      (node (ref "D3") (pin "L14") (pinfunction "PE18_L14") (pintype "passive"))
    )
    (net (code "170") (name "unconnected-(D3E-PE19-PadM13)") (class "Default")
      (node (ref "D3") (pin "M13") (pinfunction "PE19_M13") (pintype "passive"))
    )
    (net (code "171") (name "unconnected-(D3E-PE20-PadM14)") (class "Default")
      (node (ref "D3") (pin "M14") (pinfunction "PE20_M14") (pintype "passive"))
    )
    (net (code "172") (name "unconnected-(D3E-PE21-PadM15)") (class "Default")
      (node (ref "D3") (pin "M15") (pinfunction "PE21_M15") (pintype "passive"))
    )
    (net (code "173") (name "unconnected-(D3E-PE22-PadM16)") (class "Default")
      (node (ref "D3") (pin "M16") (pinfunction "PE22_M16") (pintype "passive"))
    )
    (net (code "174") (name "unconnected-(D3E-PE23-PadM17)") (class "Default")
      (node (ref "D3") (pin "M17") (pinfunction "PE23_M17") (pintype "passive"))
    )
    (net (code "175") (name "unconnected-(D3E-PE24-PadN13)") (class "Default")
      (node (ref "D3") (pin "N13") (pinfunction "PE24_N13") (pintype "passive"))
    )
    (net (code "176") (name "unconnected-(D3E-PE25-PadN14)") (class "Default")
      (node (ref "D3") (pin "N14") (pinfunction "PE25_N14") (pintype "passive"))
    )
    (net (code "177") (name "unconnected-(D3E-PE26-PadN15)") (class "Default")
      (node (ref "D3") (pin "N15") (pinfunction "PE26_N15") (pintype "passive"))
    )
    (net (code "178") (name "unconnected-(D3E-PE27-PadN16)") (class "Default")
      (node (ref "D3") (pin "N16") (pinfunction "PE27_N16") (pintype "passive"))
    )
    (net (code "179") (name "unconnected-(D3E-PE28-PadN17)") (class "Default")
      (node (ref "D3") (pin "N17") (pinfunction "PE28_N17") (pintype "passive"))
    )
    (net (code "180") (name "unconnected-(D3E-PE29-PadP15)") (class "Default")
      (node (ref "D3") (pin "P15") (pinfunction "PE29_P15") (pintype "passive"))
    )
    (net (code "181") (name "unconnected-(D3E-PE30-PadP16)") (class "Default")
      (node (ref "D3") (pin "P16") (pinfunction "PE30_P16") (pintype "passive"))
    )
    (net (code "182") (name "unconnected-(D3E-PE31-PadP17)") (class "Default")
      (node (ref "D3") (pin "P17") (pinfunction "PE31_P17") (pintype "passive"))
    )
    (net (code "183") (name "unconnected-(D3F-PF02-PadR16)") (class "Default")
      (node (ref "D3") (pin "R16") (pinfunction "PF02_R16") (pintype "passive"))
    )
    (net (code "184") (name "unconnected-(D3F-PF03-PadT16)") (class "Default")
      (node (ref "D3") (pin "T16") (pinfunction "PF03_T16") (pintype "passive"))
    )
    (net (code "185") (name "unconnected-(D3F-PF04-PadU16)") (class "Default")
      (node (ref "D3") (pin "U16") (pinfunction "PF04_U16") (pintype "passive"))
    )
    (net (code "186") (name "unconnected-(D3F-PF05-PadR15)") (class "Default")
      (node (ref "D3") (pin "R15") (pinfunction "PF05_R15") (pintype "passive"))
    )
    (net (code "187") (name "unconnected-(D3F-PF06-PadT15)") (class "Default")
      (node (ref "D3") (pin "T15") (pinfunction "PF06_T15") (pintype "passive"))
    )
    (net (code "188") (name "unconnected-(D3F-PF07-PadU15)") (class "Default")
      (node (ref "D3") (pin "U15") (pinfunction "PF07_U15") (pintype "passive"))
    )
    (net (code "189") (name "unconnected-(D3F-PF08-PadR14)") (class "Default")
      (node (ref "D3") (pin "R14") (pinfunction "PF08_R14") (pintype "passive"))
    )
    (net (code "190") (name "unconnected-(D3F-PF09-PadT14)") (class "Default")
      (node (ref "D3") (pin "T14") (pinfunction "PF09_T14") (pintype "passive"))
    )
    (net (code "191") (name "unconnected-(D3F-PF10-PadU14)") (class "Default")
      (node (ref "D3") (pin "U14") (pinfunction "PF10_U14") (pintype "passive"))
    )
    (net (code "192") (name "unconnected-(D3H-PY05-PadN6)") (class "Default")
      (node (ref "D3") (pin "N6") (pinfunction "PY05_N6") (pintype "passive"))
    )
    (net (code "193") (name "unconnected-(D3H-PY08-PadP5)") (class "Default")
      (node (ref "D3") (pin "P5") (pinfunction "PY08_P5") (pintype "passive"))
    )
    (net (code "194") (name "unconnected-(D3H-PY09-PadN5)") (class "Default")
      (node (ref "D3") (pin "N5") (pinfunction "PY09_N5") (pintype "passive"))
    )
    (net (code "195") (name "unconnected-(D3H-PY10-PadU4)") (class "Default")
      (node (ref "D3") (pin "U4") (pinfunction "PY10_U4") (pintype "passive"))
    )
    (net (code "196") (name "unconnected-(D3H-PY11-PadT4)") (class "Default")
      (node (ref "D3") (pin "T4") (pinfunction "PY11_T4") (pintype "passive"))
    )
    (net (code "197") (name "unconnected-(D3I-PZ02-PadN11)") (class "Default")
      (node (ref "D3") (pin "N11") (pinfunction "PZ02_N11") (pintype "passive"))
    )
    (net (code "198") (name "unconnected-(D3I-PZ03-PadP11)") (class "Default")
      (node (ref "D3") (pin "P11") (pinfunction "PZ03_P11") (pintype "passive"))
    )
    (net (code "199") (name "unconnected-(D3I-PZ04-PadN10)") (class "Default")
      (node (ref "D3") (pin "N10") (pinfunction "PZ04_N10") (pintype "passive"))
    )
    (net (code "200") (name "unconnected-(D3I-PZ05-PadP10)") (class "Default")
      (node (ref "D3") (pin "P10") (pinfunction "PZ05_P10") (pintype "passive"))
    )
    (net (code "201") (name "unconnected-(D3I-PZ08-PadN8)") (class "Default")
      (node (ref "D3") (pin "N8") (pinfunction "PZ08_N8") (pintype "passive"))
    )
    (net (code "202") (name "unconnected-(D3I-PZ09-PadP8)") (class "Default")
      (node (ref "D3") (pin "P8") (pinfunction "PZ09_P8") (pintype "passive"))
    )
    (net (code "203") (name "unconnected-(D3K-RTC_XTAL_IN-PadU8)") (class "Default")
      (node (ref "D3") (pin "U8") (pinfunction "RTC_XTAL_IN_U8") (pintype "passive"))
    )
    (net (code "204") (name "unconnected-(D3K-RTC_XTAL_O-PadT8)") (class "Default")
      (node (ref "D3") (pin "T8") (pinfunction "RTC_XTAL_O_T8") (pintype "passive"))
    )
  )
)
